# Sheet.net
KiCad netlist of a schematic drawn in Altium Designer
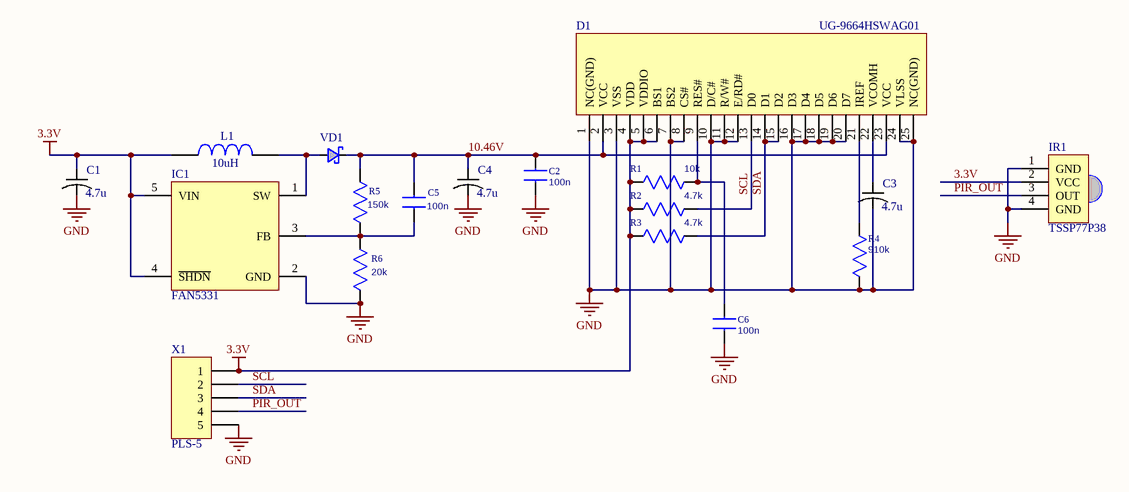
[diagram p0: Sheet.SchDoc]

(export (version "E")
  (design (tool "Eeschema 10.0.6"))
  (components
    (comp (ref "C1")
      (value "4.7u")
      (footprint "TANTALUM_CAP_SIZE_A")
      (description "Tantalum Capacitor")
      (libsource (lib "BublykIntegratedLibrary") (part "Tantalum Capacitor"))
    )
    (comp (ref "C2")
      (value "100n")
      (footprint "C_0603")
      (description "Capacitor")
      (libsource (lib "AX_Altium_v2.3") (part "C0603"))
    )
    (comp (ref "C3")
      (value "4.7u")
      (footprint "TANTALUM_CAP_SIZE_A")
      (description "Tantalum Capacitor")
      (libsource (lib "BublykIntegratedLibrary") (part "Tantalum Capacitor"))
    )
    (comp (ref "C4")
      (value "4.7u")
      (footprint "TANTALUM_CAP_SIZE_A")
      (description "Tantalum Capacitor")
      (libsource (lib "BublykIntegratedLibrary") (part "Tantalum Capacitor"))
    )
    (comp (ref "C5")
      (value "100n")
      (footprint "C_0603")
      (description "Capacitor")
      (libsource (lib "AX_Altium_v2.3") (part "C0603"))
    )
    (comp (ref "C6")
      (value "100n")
      (footprint "C_0603")
      (description "Capacitor")
      (libsource (lib "AX_Altium_v2.3") (part "C0603"))
    )
    (comp (ref "D1")
      (value "UG-9664HSWAG01")
      (footprint "UG-9664HSWAG01")
      (description "Display")
      (libsource (lib "SmartOutletIntegratedLibrary") (part "UG-9664HSWAG01"))
    )
    (comp (ref "IC1")
      (value "FAN5331")
      (footprint "SOT23-5")
      (description "High Efficiency Serial LED Driver and OLED Supp;y with 20V Integrated Switch")
      (libsource (lib "SmartOutletIntegratedLibrary") (part "FAN5331"))
    )
    (comp (ref "IR1")
      (value "TSSP77P38")
      (footprint "TSSP77P38")
      (description "IR Detector for Mid Range Proximity Sensor")
      (libsource (lib "BublykIntegratedLibrary") (part "TSSP77P38"))
    )
    (comp (ref "L1")
      (value "10uH")
      (footprint "L-7.5x7.5")
      (description "Inductor")
      (libsource (lib "SmartOutletIntegratedLibrary") (part "L"))
    )
    (comp (ref "R1")
      (value "10k")
      (footprint "R_0603")
      (description "Resistor")
      (libsource (lib "AX_Altium_v2.3") (part "R0603"))
    )
    (comp (ref "R2")
      (value "4.7k")
      (footprint "R_0603")
      (description "Resistor")
      (libsource (lib "AX_Altium_v2.3") (part "R0603"))
    )
    (comp (ref "R3")
      (value "4.7k")
      (footprint "R_0603")
      (description "Resistor")
      (libsource (lib "AX_Altium_v2.3") (part "R0603"))
    )
    (comp (ref "R4")
      (value "910k")
      (footprint "R_0603")
      (description "Resistor")
      (libsource (lib "AX_Altium_v2.3") (part "R0603"))
    )
    (comp (ref "R5")
      (value "150k")
      (footprint "R_0603")
      (description "Resistor")
      (libsource (lib "AX_Altium_v2.3") (part "R0603"))
    )
    (comp (ref "R6")
      (value "20k")
      (footprint "R_0603")
      (description "Resistor")
      (libsource (lib "AX_Altium_v2.3") (part "R0603"))
    )
    (comp (ref "VD1")
      (value "Schottky Diode")
      (footprint "DO-214AA")
      (description "SCHOTTKY BARRIER RECTIFIER")
      (libsource (lib "BublykIntegratedLibrary") (part "Schottky"))
    )
    (comp (ref "X1")
      (value "PLS-5")
      (footprint "PLS-5-3D")
      (description "Header, 5-Pin")
      (fields (field (name "PUBLISHER") "Altium Limited"))
      (libsource (lib "AX_Altium_v2.3") (part "PLS-5"))
    )
  )
  (nets
    (net (code "1") (name "/10.46V") (class "Default")
      (node (ref "C2") (pin "2") (pintype "passive"))
      (node (ref "C4") (pin "1") (pinfunction "1_1") (pintype "passive"))
      (node (ref "C5") (pin "2") (pintype "passive"))
      (node (ref "D1") (pin "2") (pinfunction "VCC_2") (pintype "passive"))
      (node (ref "D1") (pin "23") (pinfunction "VCC_23") (pintype "passive"))
      (node (ref "R5") (pin "2") (pintype "passive"))
      (node (ref "VD1") (pin "C") (pinfunction "C_C") (pintype "passive"))
    )
    (net (code "2") (name "/PIR_OUT") (class "Default")
      (node (ref "IR1") (pin "3") (pinfunction "OUT_3") (pintype "passive"))
      (node (ref "X1") (pin "4") (pinfunction "4_4") (pintype "passive"))
    )
    (net (code "3") (name "/SCL") (class "Default")
      (node (ref "D1") (pin "13") (pinfunction "D0_13") (pintype "passive"))
      (node (ref "R2") (pin "2") (pintype "passive"))
      (node (ref "X1") (pin "2") (pinfunction "2_2") (pintype "passive"))
    )
    (net (code "4") (name "/SDA") (class "Default")
      (node (ref "D1") (pin "14") (pinfunction "D1_14") (pintype "passive"))
      (node (ref "D1") (pin "15") (pinfunction "D2_15") (pintype "passive"))
      (node (ref "R3") (pin "2") (pintype "passive"))
      (node (ref "X1") (pin "3") (pinfunction "3_3") (pintype "passive"))
    )
    (net (code "5") (name "3.3V") (class "Default")
      (node (ref "C1") (pin "1") (pinfunction "1_1") (pintype "passive"))
      (node (ref "D1") (pin "4") (pinfunction "VDD_4") (pintype "passive"))
      (node (ref "D1") (pin "5") (pinfunction "VDDIO_5") (pintype "passive"))
      (node (ref "D1") (pin "6") (pinfunction "BS1_6") (pintype "passive"))
      (node (ref "IC1") (pin "4") (pinfunction "~{SHDN}_4") (pintype "passive"))
      (node (ref "IC1") (pin "5") (pinfunction "VIN_5") (pintype "passive"))
      (node (ref "IR1") (pin "2") (pinfunction "VCC_2") (pintype "passive"))
      (node (ref "L1") (pin "1") (pinfunction "1_1") (pintype "passive"))
      (node (ref "R1") (pin "1") (pintype "passive"))
      (node (ref "R2") (pin "1") (pintype "passive"))
      (node (ref "R3") (pin "1") (pintype "passive"))
      (node (ref "X1") (pin "1") (pinfunction "1_1") (pintype "passive"))
    )
    (net (code "6") (name "GND") (class "Default")
      (node (ref "C1") (pin "2") (pinfunction "2_2") (pintype "passive"))
      (node (ref "C2") (pin "1") (pintype "passive"))
      (node (ref "C3") (pin "2") (pinfunction "2_2") (pintype "passive"))
      (node (ref "C4") (pin "2") (pinfunction "2_2") (pintype "passive"))
      (node (ref "C6") (pin "2") (pintype "passive"))
      (node (ref "D1") (pin "1") (pinfunction "NC(GND)_1") (pintype "passive"))
      (node (ref "D1") (pin "10") (pinfunction "D/C#_10") (pintype "passive"))
      (node (ref "D1") (pin "11") (pinfunction "R/W#_11") (pintype "passive"))
      (node (ref "D1") (pin "12") (pinfunction "E/RD#_12") (pintype "passive"))
      (node (ref "D1") (pin "16") (pinfunction "D3_16") (pintype "passive"))
      (node (ref "D1") (pin "17") (pinfunction "D4_17") (pintype "passive"))
      (node (ref "D1") (pin "18") (pinfunction "D5_18") (pintype "passive"))
      (node (ref "D1") (pin "19") (pinfunction "D6_19") (pintype "passive"))
      (node (ref "D1") (pin "20") (pinfunction "D7_20") (pintype "passive"))
      (node (ref "D1") (pin "24") (pinfunction "VLSS_24") (pintype "passive"))
      (node (ref "D1") (pin "25") (pinfunction "NC(GND)_25") (pintype "passive"))
      (node (ref "D1") (pin "3") (pinfunction "VSS_3") (pintype "passive"))
      (node (ref "D1") (pin "7") (pinfunction "BS2_7") (pintype "passive"))
      (node (ref "D1") (pin "8") (pinfunction "CS#_8") (pintype "passive"))
      (node (ref "IC1") (pin "2") (pinfunction "GND_2") (pintype "passive"))
      (node (ref "IR1") (pin "1") (pinfunction "GND_1") (pintype "passive"))
      (node (ref "IR1") (pin "4") (pinfunction "GND_4") (pintype "passive"))
      (node (ref "R4") (pin "2") (pintype "passive"))
      (node (ref "R6") (pin "1") (pintype "passive"))
      (node (ref "X1") (pin "5") (pinfunction "5_5") (pintype "passive"))
    )
    (net (code "7") (name "Net-(D1-IREF)") (class "Default")
      (node (ref "D1") (pin "21") (pinfunction "IREF_21") (pintype "passive"))
      (node (ref "R4") (pin "1") (pintype "passive"))
    )
    (net (code "8") (name "Net-(D1-RES#)") (class "Default")
      (node (ref "C6") (pin "1") (pintype "passive"))
      (node (ref "D1") (pin "9") (pinfunction "RES#_9") (pintype "passive"))
      (node (ref "R1") (pin "2") (pintype "passive"))
    )
    (net (code "9") (name "Net-(D1-VCOMH)") (class "Default")
      (node (ref "C3") (pin "1") (pinfunction "1_1") (pintype "passive"))
      (node (ref "D1") (pin "22") (pinfunction "VCOMH_22") (pintype "passive"))
    )
    (net (code "10") (name "Net-(IC1-FB)") (class "Default")
      (node (ref "C5") (pin "1") (pintype "passive"))
      (node (ref "IC1") (pin "3") (pinfunction "FB_3") (pintype "passive"))
      (node (ref "R5") (pin "1") (pintype "passive"))
      (node (ref "R6") (pin "2") (pintype "passive"))
    )
    (net (code "11") (name "Net-(IC1-SW)") (class "Default")
      (node (ref "IC1") (pin "1") (pinfunction "SW_1") (pintype "passive"))
      (node (ref "L1") (pin "2") (pinfunction "2_2") (pintype "passive"))
      (node (ref "VD1") (pin "A") (pinfunction "A_A") (pintype "passive"))
    )
  )
)
